# SH2-MCU.net
KiCad netlist of a schematic drawn in Altium Designer
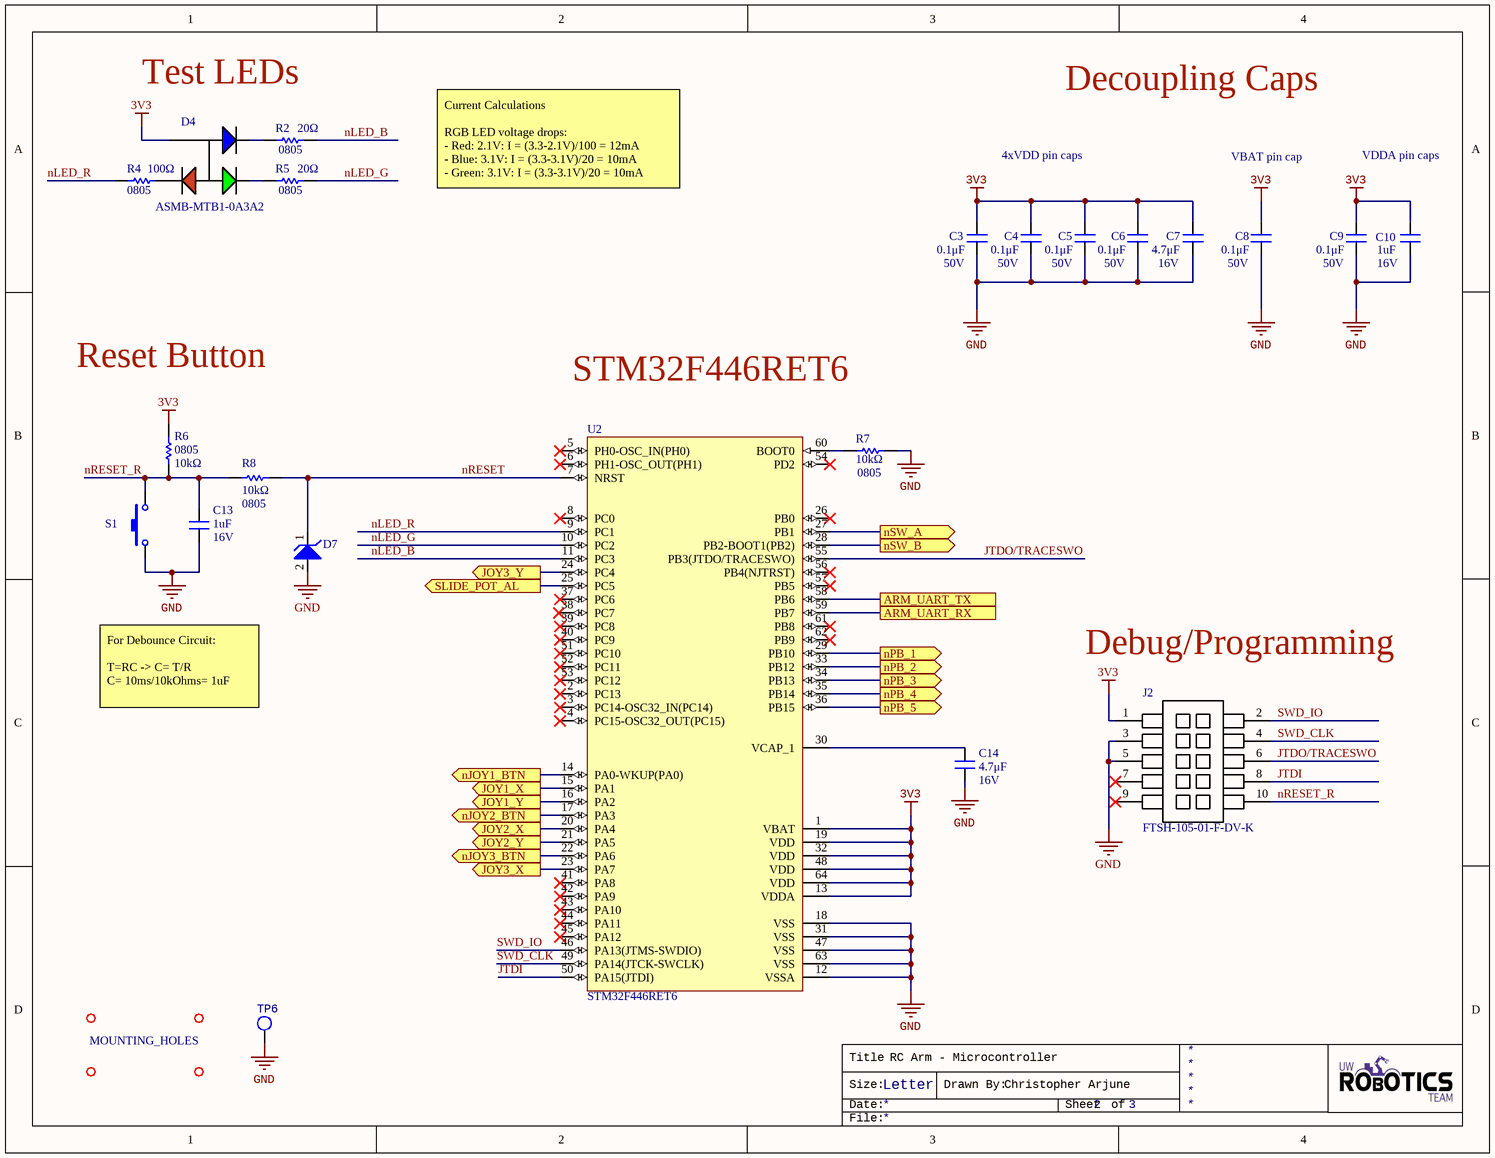
[diagram p0: SH2-MCU.SchDoc]

(export (version "E")
  (design (tool "Eeschema 10.0.6"))
  (components
    (comp (ref "C3")
      (value "0.1μF")
      (footprint "CAPC2012X140N")
      (description "CAP CER 0.1UF 50V X7R 0805")
      (fields (field (name "TOLERANCE") "10%") (field (name "VOLTAGE RATING") "50V"))
      (libsource (lib "UWRT_Schematic_Library_2020") (part "CAP_0.1uF_50V_0805"))
    )
    (comp (ref "C4")
      (value "0.1μF")
      (footprint "CAPC2012X140N")
      (description "CAP CER 0.1UF 50V X7R 0805")
      (fields (field (name "TOLERANCE") "10%") (field (name "VOLTAGE RATING") "50V"))
      (libsource (lib "UWRT_Schematic_Library_2020") (part "CAP_0.1uF_50V_0805"))
    )
    (comp (ref "C5")
      (value "0.1μF")
      (footprint "CAPC2012X140N")
      (description "CAP CER 0.1UF 50V X7R 0805")
      (fields (field (name "TOLERANCE") "10%") (field (name "VOLTAGE RATING") "50V"))
      (libsource (lib "UWRT_Schematic_Library_2020") (part "CAP_0.1uF_50V_0805"))
    )
    (comp (ref "C6")
      (value "0.1μF")
      (footprint "CAPC2012X140N")
      (description "CAP CER 0.1UF 50V X7R 0805")
      (fields (field (name "TOLERANCE") "10%") (field (name "VOLTAGE RATING") "50V"))
      (libsource (lib "UWRT_Schematic_Library_2020") (part "CAP_0.1uF_50V_0805"))
    )
    (comp (ref "C7")
      (value "4.7μF")
      (footprint "CAPC2012X140N")
      (description "CAP CER 4.7UF 16V X5R 0805")
      (fields
        (field (name "TOLERANCE") "10%")
        (field (name "VOLTAGE RATING") "16V")
        (field (name "Comment") "CAP_4.7uF_16V_0805")
      )
      (libsource (lib "UWRT_Schematic_Library_2020") (part "CAP_4.7uF_16V_0805"))
    )
    (comp (ref "C8")
      (value "0.1μF")
      (footprint "CAPC2012X140N")
      (description "CAP CER 0.1UF 50V X7R 0805")
      (fields (field (name "TOLERANCE") "10%") (field (name "VOLTAGE RATING") "50V"))
      (libsource (lib "UWRT_Schematic_Library_2020") (part "CAP_0.1uF_50V_0805"))
    )
    (comp (ref "C9")
      (value "0.1μF")
      (footprint "CAPC2012X140N")
      (description "CAP CER 0.1UF 50V X7R 0805")
      (fields (field (name "TOLERANCE") "10%") (field (name "VOLTAGE RATING") "50V"))
      (libsource (lib "UWRT_Schematic_Library_2020") (part "CAP_0.1uF_50V_0805"))
    )
    (comp (ref "C10")
      (value "1uF")
      (footprint "CAPC2012X140N")
      (description "CAP CER 1UF 16V X7R 0805")
      (fields
        (field (name "TOLERANCE") "10%")
        (field (name "VOLTAGE RATING") "16V")
        (field (name "Comment") "CAP_1uF_16V_0805")
      )
      (libsource (lib "UWRT_Schematic_Library_2020") (part "CAP_1uF_16V_0805"))
    )
    (comp (ref "C13")
      (value "1uF")
      (footprint "CAPC2012X140N")
      (description "CAP CER 1UF 16V X7R 0805")
      (fields
        (field (name "TOLERANCE") "10%")
        (field (name "VOLTAGE RATING") "16V")
        (field (name "Comment") "CAP_1uF_16V_0805")
      )
      (libsource (lib "UWRT_Schematic_Library_2020") (part "CAP_1uF_16V_0805"))
    )
    (comp (ref "C14")
      (value "4.7μF")
      (footprint "CAPC2012X140N")
      (description "CAP CER 4.7UF 16V X5R 0805")
      (fields
        (field (name "TOLERANCE") "10%")
        (field (name "VOLTAGE RATING") "16V")
        (field (name "Comment") "CAP_4.7uF_16V_0805")
      )
      (libsource (lib "UWRT_Schematic_Library_2020") (part "CAP_4.7uF_16V_0805"))
    )
    (comp (ref "D4")
      (value "LED_RGB")
      (footprint "LED_RGB")
      (description "LED RGB DIFFUSED 4PLCC SMD")
      (fields (field (name "MANUFACTURER PART NUMBER 1") "ASMB-MTB1-0A3A2"))
      (libsource (lib "UWRT_Schematic_Library_2020") (part "LED_RGB"))
    )
    (comp (ref "D7")
      (value "TVS_DIODE_UNIDIR_3.3V")
      (footprint "SOD523")
      (description "TVS DIODE 3.3V 14.1V SOD523. Used to protect each connector input line going into the MCU.")
      (libsource (lib "UWRT_Schematic_Library_2020") (part "TVS_DIODE_UNIDIR_3.3V"))
    )
    (comp (ref "J2")
      (value "CON_PROGRAMMING")
      (footprint "FTSH-105-01-F-DV-K-P-TR")
      (fields (field (name "MANUFACTURER PART NUMBER 1") "FTSH-105-01-F-DV-K"))
      (libsource (lib "UWRT_Schematic_Library_2020") (part "CON_PROGRAMMING"))
    )
    (comp (ref "MH1")
      (value "MOUNTING_HOLES")
      (footprint "MOUNTING_HOLE")
      (description "6cm x 6cm")
      (libsource (lib "UWRT_Schematic_Library_2020") (part "MOUNTING_HOLES"))
    )
    (comp (ref "MH2")
      (value "MOUNTING_HOLES")
      (footprint "MOUNTING_HOLE")
      (description "6cm x 6cm")
      (libsource (lib "UWRT_Schematic_Library_2020") (part "MOUNTING_HOLES"))
    )
    (comp (ref "MH3")
      (value "MOUNTING_HOLES")
      (footprint "MOUNTING_HOLE")
      (description "6cm x 6cm")
      (libsource (lib "UWRT_Schematic_Library_2020") (part "MOUNTING_HOLES"))
    )
    (comp (ref "MH4")
      (value "MOUNTING_HOLES")
      (footprint "MOUNTING_HOLE")
      (description "6cm x 6cm")
      (libsource (lib "UWRT_Schematic_Library_2020") (part "MOUNTING_HOLES"))
    )
    (comp (ref "R2")
      (value "20Ω")
      (footprint "RESC2012X60N")
      (description "RES SMD 20 OHM 1% 1/8W 0805")
      (fields
        (field (name "CASE CODE (IMPERIAL)") "0805")
        (field (name "TOLERANCE") "1%")
        (field (name "Comment") "RES_20Ω_0805")
      )
      (libsource (lib "UWRT_Schematic_Library_2020") (part "RES_20Ω_0805"))
    )
    (comp (ref "R4")
      (value "100Ω")
      (footprint "RESC2012X60N")
      (description "RES SMD 100 OHM 1% 1/8W 0805")
      (fields (field (name "CASE CODE (IMPERIAL)") "0805") (field (name "Comment") "RES_100Ω_0805"))
      (libsource (lib "UWRT_Schematic_Library_2020") (part "RES_100Ω_0805"))
    )
    (comp (ref "R5")
      (value "20Ω")
      (footprint "RESC2012X60N")
      (description "RES SMD 20 OHM 1% 1/8W 0805")
      (fields
        (field (name "CASE CODE (IMPERIAL)") "0805")
        (field (name "TOLERANCE") "1%")
        (field (name "Comment") "RES_20Ω_0805")
      )
      (libsource (lib "UWRT_Schematic_Library_2020") (part "RES_20Ω_0805"))
    )
    (comp (ref "R6")
      (value "10kΩ")
      (footprint "RESC2012X60N")
      (description "RES SMD 10K OHM 1% 1/8W 0805")
      (fields
        (field (name "CASE CODE (IMPERIAL)") "0805")
        (field (name "TOLERANCE") "1%")
        (field (name "Comment") "RES_10kΩ_0805")
      )
      (libsource (lib "UWRT_Schematic_Library_2020") (part "RES_10kΩ_0805"))
    )
    (comp (ref "R7")
      (value "10kΩ")
      (footprint "RESC2012X60N")
      (description "RES SMD 10K OHM 1% 1/8W 0805")
      (fields
        (field (name "CASE CODE (IMPERIAL)") "0805")
        (field (name "TOLERANCE") "1%")
        (field (name "Comment") "RES_10kΩ_0805")
      )
      (libsource (lib "UWRT_Schematic_Library_2020") (part "RES_10kΩ_0805"))
    )
    (comp (ref "R8")
      (value "10kΩ")
      (footprint "RESC2012X60N")
      (description "RES SMD 10K OHM 1% 1/8W 0805")
      (fields
        (field (name "CASE CODE (IMPERIAL)") "0805")
        (field (name "TOLERANCE") "1%")
        (field (name "Comment") "RES_10kΩ_0805")
      )
      (libsource (lib "UWRT_Schematic_Library_2020") (part "RES_10kΩ_0805"))
    )
    (comp (ref "S1")
      (value "SW_TACTILE")
      (footprint "B3U-1000P")
      (description "Tactile Switch (Grey)")
      (libsource (lib "UWRT_Schematic_Library_2020") (part "SW_TACTILE"))
    )
    (comp (ref "TP6")
      (value "TESTPOINT_LOOP")
      (footprint "TESTPOINT_LOOP")
      (description "Loop testpoint through-hole pad")
      (libsource (lib "UWRT_Schematic_Library_2020") (part "TESTPOINT_LOOP"))
    )
    (comp (ref "U2")
      (value "STM32F446RET6")
      (footprint "STM-LQFP64_L")
      (libsource (lib "UWRT_Schematic_Library_2020") (part "MCU_STM32F446RET6"))
    )
  )
  (nets
    (net (code "1") (name "/ARM_UART_RX") (class "Default")
      (node (ref "U2") (pin "59") (pinfunction "PB7_59") (pintype "bidirectional"))
    )
    (net (code "2") (name "/ARM_UART_TX") (class "Default")
      (node (ref "U2") (pin "58") (pinfunction "PB6_58") (pintype "bidirectional"))
    )
    (net (code "3") (name "/JOY1_X") (class "Default")
      (node (ref "U2") (pin "15") (pinfunction "PA1_15") (pintype "bidirectional"))
    )
    (net (code "4") (name "/JOY1_Y") (class "Default")
      (node (ref "U2") (pin "16") (pinfunction "PA2_16") (pintype "bidirectional"))
    )
    (net (code "5") (name "/JOY2_X") (class "Default")
      (node (ref "U2") (pin "20") (pinfunction "PA4_20") (pintype "bidirectional"))
    )
    (net (code "6") (name "/JOY2_Y") (class "Default")
      (node (ref "U2") (pin "21") (pinfunction "PA5_21") (pintype "bidirectional"))
    )
    (net (code "7") (name "/JOY3_X") (class "Default")
      (node (ref "U2") (pin "23") (pinfunction "PA7_23") (pintype "bidirectional"))
    )
    (net (code "8") (name "/JOY3_Y") (class "Default")
      (node (ref "U2") (pin "24") (pinfunction "PC4_24") (pintype "bidirectional"))
    )
    (net (code "9") (name "/JTDI") (class "Default")
      (node (ref "J2") (pin "8") (pinfunction "8_8") (pintype "passive"))
      (node (ref "U2") (pin "50") (pinfunction "PA15(JTDI)_50") (pintype "bidirectional"))
    )
    (net (code "10") (name "/JTDO{slash}TRACESWO") (class "Default")
      (node (ref "J2") (pin "6") (pinfunction "6_6") (pintype "passive"))
      (node (ref "U2") (pin "55") (pinfunction "PB3(JTDO/TRACESWO)_55") (pintype "bidirectional"))
    )
    (net (code "11") (name "/SLIDE_POT_AL") (class "Default")
      (node (ref "U2") (pin "25") (pinfunction "PC5_25") (pintype "bidirectional"))
    )
    (net (code "12") (name "/SWD_CLK") (class "Default")
      (node (ref "J2") (pin "4") (pinfunction "4_4") (pintype "passive"))
      (node (ref "U2") (pin "49") (pinfunction "PA14(JTCK-SWCLK)_49") (pintype "bidirectional"))
    )
    (net (code "13") (name "/SWD_IO") (class "Default")
      (node (ref "J2") (pin "2") (pinfunction "2_2") (pintype "passive"))
      (node (ref "U2") (pin "46") (pinfunction "PA13(JTMS-SWDIO)_46") (pintype "bidirectional"))
    )
    (net (code "14") (name "/nJOY1_BTN") (class "Default")
      (node (ref "U2") (pin "14") (pinfunction "PA0-WKUP(PA0)_14") (pintype "bidirectional"))
    )
    (net (code "15") (name "/nJOY2_BTN") (class "Default")
      (node (ref "U2") (pin "17") (pinfunction "PA3_17") (pintype "bidirectional"))
    )
    (net (code "16") (name "/nJOY3_BTN") (class "Default")
      (node (ref "U2") (pin "22") (pinfunction "PA6_22") (pintype "bidirectional"))
    )
    (net (code "17") (name "/nLED_B") (class "Default")
      (node (ref "R2") (pin "2") (pinfunction "2_2") (pintype "passive"))
      (node (ref "U2") (pin "11") (pinfunction "PC3_11") (pintype "bidirectional"))
    )
    (net (code "18") (name "/nLED_G") (class "Default")
      (node (ref "R5") (pin "2") (pinfunction "2_2") (pintype "passive"))
      (node (ref "U2") (pin "10") (pinfunction "PC2_10") (pintype "bidirectional"))
    )
    (net (code "19") (name "/nLED_R") (class "Default")
      (node (ref "R4") (pin "1") (pinfunction "1_1") (pintype "passive"))
      (node (ref "U2") (pin "9") (pinfunction "PC1_9") (pintype "bidirectional"))
    )
    (net (code "20") (name "/nPB_1") (class "Default")
      (node (ref "U2") (pin "29") (pinfunction "PB10_29") (pintype "bidirectional"))
    )
    (net (code "21") (name "/nPB_2") (class "Default")
      (node (ref "U2") (pin "33") (pinfunction "PB12_33") (pintype "bidirectional"))
    )
    (net (code "22") (name "/nPB_3") (class "Default")
      (node (ref "U2") (pin "34") (pinfunction "PB13_34") (pintype "bidirectional"))
    )
    (net (code "23") (name "/nPB_4") (class "Default")
      (node (ref "U2") (pin "35") (pinfunction "PB14_35") (pintype "bidirectional"))
    )
    (net (code "24") (name "/nPB_5") (class "Default")
      (node (ref "U2") (pin "36") (pinfunction "PB15_36") (pintype "bidirectional"))
    )
    (net (code "25") (name "/nRESET") (class "Default")
      (node (ref "D7") (pin "1") (pinfunction "1_1") (pintype "passive"))
      (node (ref "R8") (pin "2") (pinfunction "2_2") (pintype "passive"))
      (node (ref "U2") (pin "7") (pinfunction "NRST_7") (pintype "bidirectional"))
    )
    (net (code "26") (name "/nRESET_R") (class "Default")
      (node (ref "C13") (pin "2") (pinfunction "2_2") (pintype "passive"))
      (node (ref "J2") (pin "10") (pinfunction "10_10") (pintype "passive"))
      (node (ref "R6") (pin "1") (pinfunction "1_1") (pintype "passive"))
      (node (ref "R8") (pin "1") (pinfunction "1_1") (pintype "passive"))
      (node (ref "S1") (pin "1") (pinfunction "1_1") (pintype "passive"))
    )
    (net (code "27") (name "/nSW_A") (class "Default")
      (node (ref "U2") (pin "27") (pinfunction "PB1_27") (pintype "bidirectional"))
    )
    (net (code "28") (name "/nSW_B") (class "Default")
      (node (ref "U2") (pin "28") (pinfunction "PB2-BOOT1(PB2)_28") (pintype "bidirectional"))
    )
    (net (code "29") (name "3V3") (class "Default")
      (node (ref "C10") (pin "2") (pinfunction "2_2") (pintype "passive"))
      (node (ref "C3") (pin "2") (pinfunction "2_2") (pintype "passive"))
      (node (ref "C4") (pin "2") (pinfunction "2_2") (pintype "passive"))
      (node (ref "C5") (pin "2") (pinfunction "2_2") (pintype "passive"))
      (node (ref "C6") (pin "2") (pinfunction "2_2") (pintype "passive"))
      (node (ref "C7") (pin "2") (pinfunction "2_2") (pintype "passive"))
      (node (ref "C8") (pin "2") (pinfunction "2_2") (pintype "passive"))
      (node (ref "C9") (pin "2") (pinfunction "2_2") (pintype "passive"))
      (node (ref "D4") (pin "4") (pinfunction "9_4") (pintype "passive"))
      (node (ref "J2") (pin "1") (pinfunction "1_1") (pintype "passive"))
      (node (ref "R6") (pin "2") (pinfunction "2_2") (pintype "passive"))
      (node (ref "U2") (pin "1") (pinfunction "VBAT_1") (pintype "power_in"))
      (node (ref "U2") (pin "13") (pinfunction "VDDA_13") (pintype "power_in"))
      (node (ref "U2") (pin "19") (pinfunction "VDD_19") (pintype "power_in"))
      (node (ref "U2") (pin "32") (pinfunction "VDD_32") (pintype "power_in"))
      (node (ref "U2") (pin "48") (pinfunction "VDD_48") (pintype "power_in"))
      (node (ref "U2") (pin "64") (pinfunction "VDD_64") (pintype "power_in"))
    )
    (net (code "30") (name "GND") (class "Default")
      (node (ref "C10") (pin "1") (pinfunction "1_1") (pintype "passive"))
      (node (ref "C13") (pin "1") (pinfunction "1_1") (pintype "passive"))
      (node (ref "C14") (pin "1") (pinfunction "1_1") (pintype "passive"))
      (node (ref "C3") (pin "1") (pinfunction "1_1") (pintype "passive"))
      (node (ref "C4") (pin "1") (pinfunction "1_1") (pintype "passive"))
      (node (ref "C5") (pin "1") (pinfunction "1_1") (pintype "passive"))
      (node (ref "C6") (pin "1") (pinfunction "1_1") (pintype "passive"))
      (node (ref "C7") (pin "1") (pinfunction "1_1") (pintype "passive"))
      (node (ref "C8") (pin "1") (pinfunction "1_1") (pintype "passive"))
      (node (ref "C9") (pin "1") (pinfunction "1_1") (pintype "passive"))
      (node (ref "D7") (pin "2") (pinfunction "2_2") (pintype "passive"))
      (node (ref "J2") (pin "3") (pinfunction "3_3") (pintype "passive"))
      (node (ref "J2") (pin "5") (pinfunction "5_5") (pintype "passive"))
      (node (ref "R7") (pin "2") (pinfunction "2_2") (pintype "passive"))
      (node (ref "S1") (pin "2") (pinfunction "2_2") (pintype "passive"))
      (node (ref "TP6") (pin "1") (pintype "passive"))
      (node (ref "U2") (pin "12") (pinfunction "VSSA_12") (pintype "power_in"))
      (node (ref "U2") (pin "18") (pinfunction "VSS_18") (pintype "power_in"))
      (node (ref "U2") (pin "31") (pinfunction "VSS_31") (pintype "power_in"))
      (node (ref "U2") (pin "47") (pinfunction "VSS_47") (pintype "power_in"))
      (node (ref "U2") (pin "63") (pinfunction "VSS_63") (pintype "power_in"))
    )
    (net (code "31") (name "Net-(D4-10)") (class "Default")
      (node (ref "D4") (pin "3") (pinfunction "10_3") (pintype "passive"))
      (node (ref "R2") (pin "1") (pinfunction "1_1") (pintype "passive"))
    )
    (net (code "32") (name "Net-(D4-11)") (class "Default")
      (node (ref "D4") (pin "1") (pinfunction "11_1") (pintype "passive"))
      (node (ref "R4") (pin "2") (pinfunction "2_2") (pintype "passive"))
    )
    (net (code "33") (name "Net-(D4-12)") (class "Default")
      (node (ref "D4") (pin "2") (pinfunction "12_2") (pintype "passive"))
      (node (ref "R5") (pin "1") (pinfunction "1_1") (pintype "passive"))
    )
    (net (code "34") (name "Net-(U2-BOOT0)") (class "Default")
      (node (ref "R7") (pin "1") (pinfunction "1_1") (pintype "passive"))
      (node (ref "U2") (pin "60") (pinfunction "BOOT0_60") (pintype "input"))
    )
    (net (code "35") (name "Net-(U2-VCAP_1)") (class "Default")
      (node (ref "C14") (pin "2") (pinfunction "2_2") (pintype "passive"))
      (node (ref "U2") (pin "30") (pinfunction "VCAP_1_30") (pintype "passive"))
    )
    (net (code "36") (name "unconnected-(J2-Pad7)") (class "Default")
      (node (ref "J2") (pin "7") (pinfunction "7_7") (pintype "passive+no_connect"))
    )
    (net (code "37") (name "unconnected-(J2-Pad9)") (class "Default")
      (node (ref "J2") (pin "9") (pinfunction "9_9") (pintype "passive+no_connect"))
    )
    (net (code "38") (name "unconnected-(U2-PA8-Pad41)") (class "Default")
      (node (ref "U2") (pin "41") (pinfunction "PA8_41") (pintype "bidirectional+no_connect"))
    )
    (net (code "39") (name "unconnected-(U2-PA9-Pad42)") (class "Default")
      (node (ref "U2") (pin "42") (pinfunction "PA9_42") (pintype "bidirectional+no_connect"))
    )
    (net (code "40") (name "unconnected-(U2-PA10-Pad43)") (class "Default")
      (node (ref "U2") (pin "43") (pinfunction "PA10_43") (pintype "bidirectional+no_connect"))
    )
    (net (code "41") (name "unconnected-(U2-PA11-Pad44)") (class "Default")
      (node (ref "U2") (pin "44") (pinfunction "PA11_44") (pintype "bidirectional+no_connect"))
    )
    (net (code "42") (name "unconnected-(U2-PA12-Pad45)") (class "Default")
      (node (ref "U2") (pin "45") (pinfunction "PA12_45") (pintype "bidirectional+no_connect"))
    )
    (net (code "43") (name "unconnected-(U2-PB0-Pad26)") (class "Default")
      (node (ref "U2") (pin "26") (pinfunction "PB0_26") (pintype "bidirectional+no_connect"))
    )
    (net (code "44") (name "unconnected-(U2-PB4(NJTRST)-Pad56)") (class "Default")
      (node (ref "U2") (pin "56") (pinfunction "PB4(NJTRST)_56") (pintype "bidirectional+no_connect"))
    )
    (net (code "45") (name "unconnected-(U2-PB5-Pad57)") (class "Default")
      (node (ref "U2") (pin "57") (pinfunction "PB5_57") (pintype "bidirectional+no_connect"))
    )
    (net (code "46") (name "unconnected-(U2-PB8-Pad61)") (class "Default")
      (node (ref "U2") (pin "61") (pinfunction "PB8_61") (pintype "bidirectional+no_connect"))
    )
    (net (code "47") (name "unconnected-(U2-PB9-Pad62)") (class "Default")
      (node (ref "U2") (pin "62") (pinfunction "PB9_62") (pintype "bidirectional+no_connect"))
    )
    (net (code "48") (name "unconnected-(U2-PC0-Pad8)") (class "Default")
      (node (ref "U2") (pin "8") (pinfunction "PC0_8") (pintype "bidirectional+no_connect"))
    )
    (net (code "49") (name "unconnected-(U2-PC6-Pad37)") (class "Default")
      (node (ref "U2") (pin "37") (pinfunction "PC6_37") (pintype "bidirectional+no_connect"))
    )
    (net (code "50") (name "unconnected-(U2-PC7-Pad38)") (class "Default")
      (node (ref "U2") (pin "38") (pinfunction "PC7_38") (pintype "bidirectional"))
    )
    (net (code "51") (name "unconnected-(U2-PC8-Pad39)") (class "Default")
      (node (ref "U2") (pin "39") (pinfunction "PC8_39") (pintype "bidirectional+no_connect"))
    )
    (net (code "52") (name "unconnected-(U2-PC9-Pad40)") (class "Default")
      (node (ref "U2") (pin "40") (pinfunction "PC9_40") (pintype "bidirectional+no_connect"))
    )
    (net (code "53") (name "unconnected-(U2-PC10-Pad51)") (class "Default")
      (node (ref "U2") (pin "51") (pinfunction "PC10_51") (pintype "bidirectional+no_connect"))
    )
    (net (code "54") (name "unconnected-(U2-PC11-Pad52)") (class "Default")
      (node (ref "U2") (pin "52") (pinfunction "PC11_52") (pintype "bidirectional+no_connect"))
    )
    (net (code "55") (name "unconnected-(U2-PC12-Pad53)") (class "Default")
      (node (ref "U2") (pin "53") (pinfunction "PC12_53") (pintype "bidirectional+no_connect"))
    )
    (net (code "56") (name "unconnected-(U2-PC13-Pad2)") (class "Default")
      (node (ref "U2") (pin "2") (pinfunction "PC13_2") (pintype "bidirectional+no_connect"))
    )
    (net (code "57") (name "unconnected-(U2-PC14-OSC32_IN(PC14)-Pad3)") (class "Default")
      (node (ref "U2") (pin "3") (pinfunction "PC14-OSC32_IN(PC14)_3") (pintype "bidirectional+no_connect"))
    )
    (net (code "58") (name "unconnected-(U2-PC15-OSC32_OUT(PC15)-Pad4)") (class "Default")
      (node (ref "U2") (pin "4") (pinfunction "PC15-OSC32_OUT(PC15)_4") (pintype "bidirectional+no_connect"))
    )
    (net (code "59") (name "unconnected-(U2-PD2-Pad54)") (class "Default")
      (node (ref "U2") (pin "54") (pinfunction "PD2_54") (pintype "bidirectional+no_connect"))
    )
    (net (code "60") (name "unconnected-(U2-PH0-OSC_IN(PH0)-Pad5)") (class "Default")
      (node (ref "U2") (pin "5") (pinfunction "PH0-OSC_IN(PH0)_5") (pintype "bidirectional+no_connect"))
    )
    (net (code "61") (name "unconnected-(U2-PH1-OSC_OUT(PH1)-Pad6)") (class "Default")
      (node (ref "U2") (pin "6") (pinfunction "PH1-OSC_OUT(PH1)_6") (pintype "bidirectional+no_connect"))
    )
  )
)
